# SCH_nfc_card_2024-08-14.net
KiCad netlist of a schematic drawn in EasyEDA
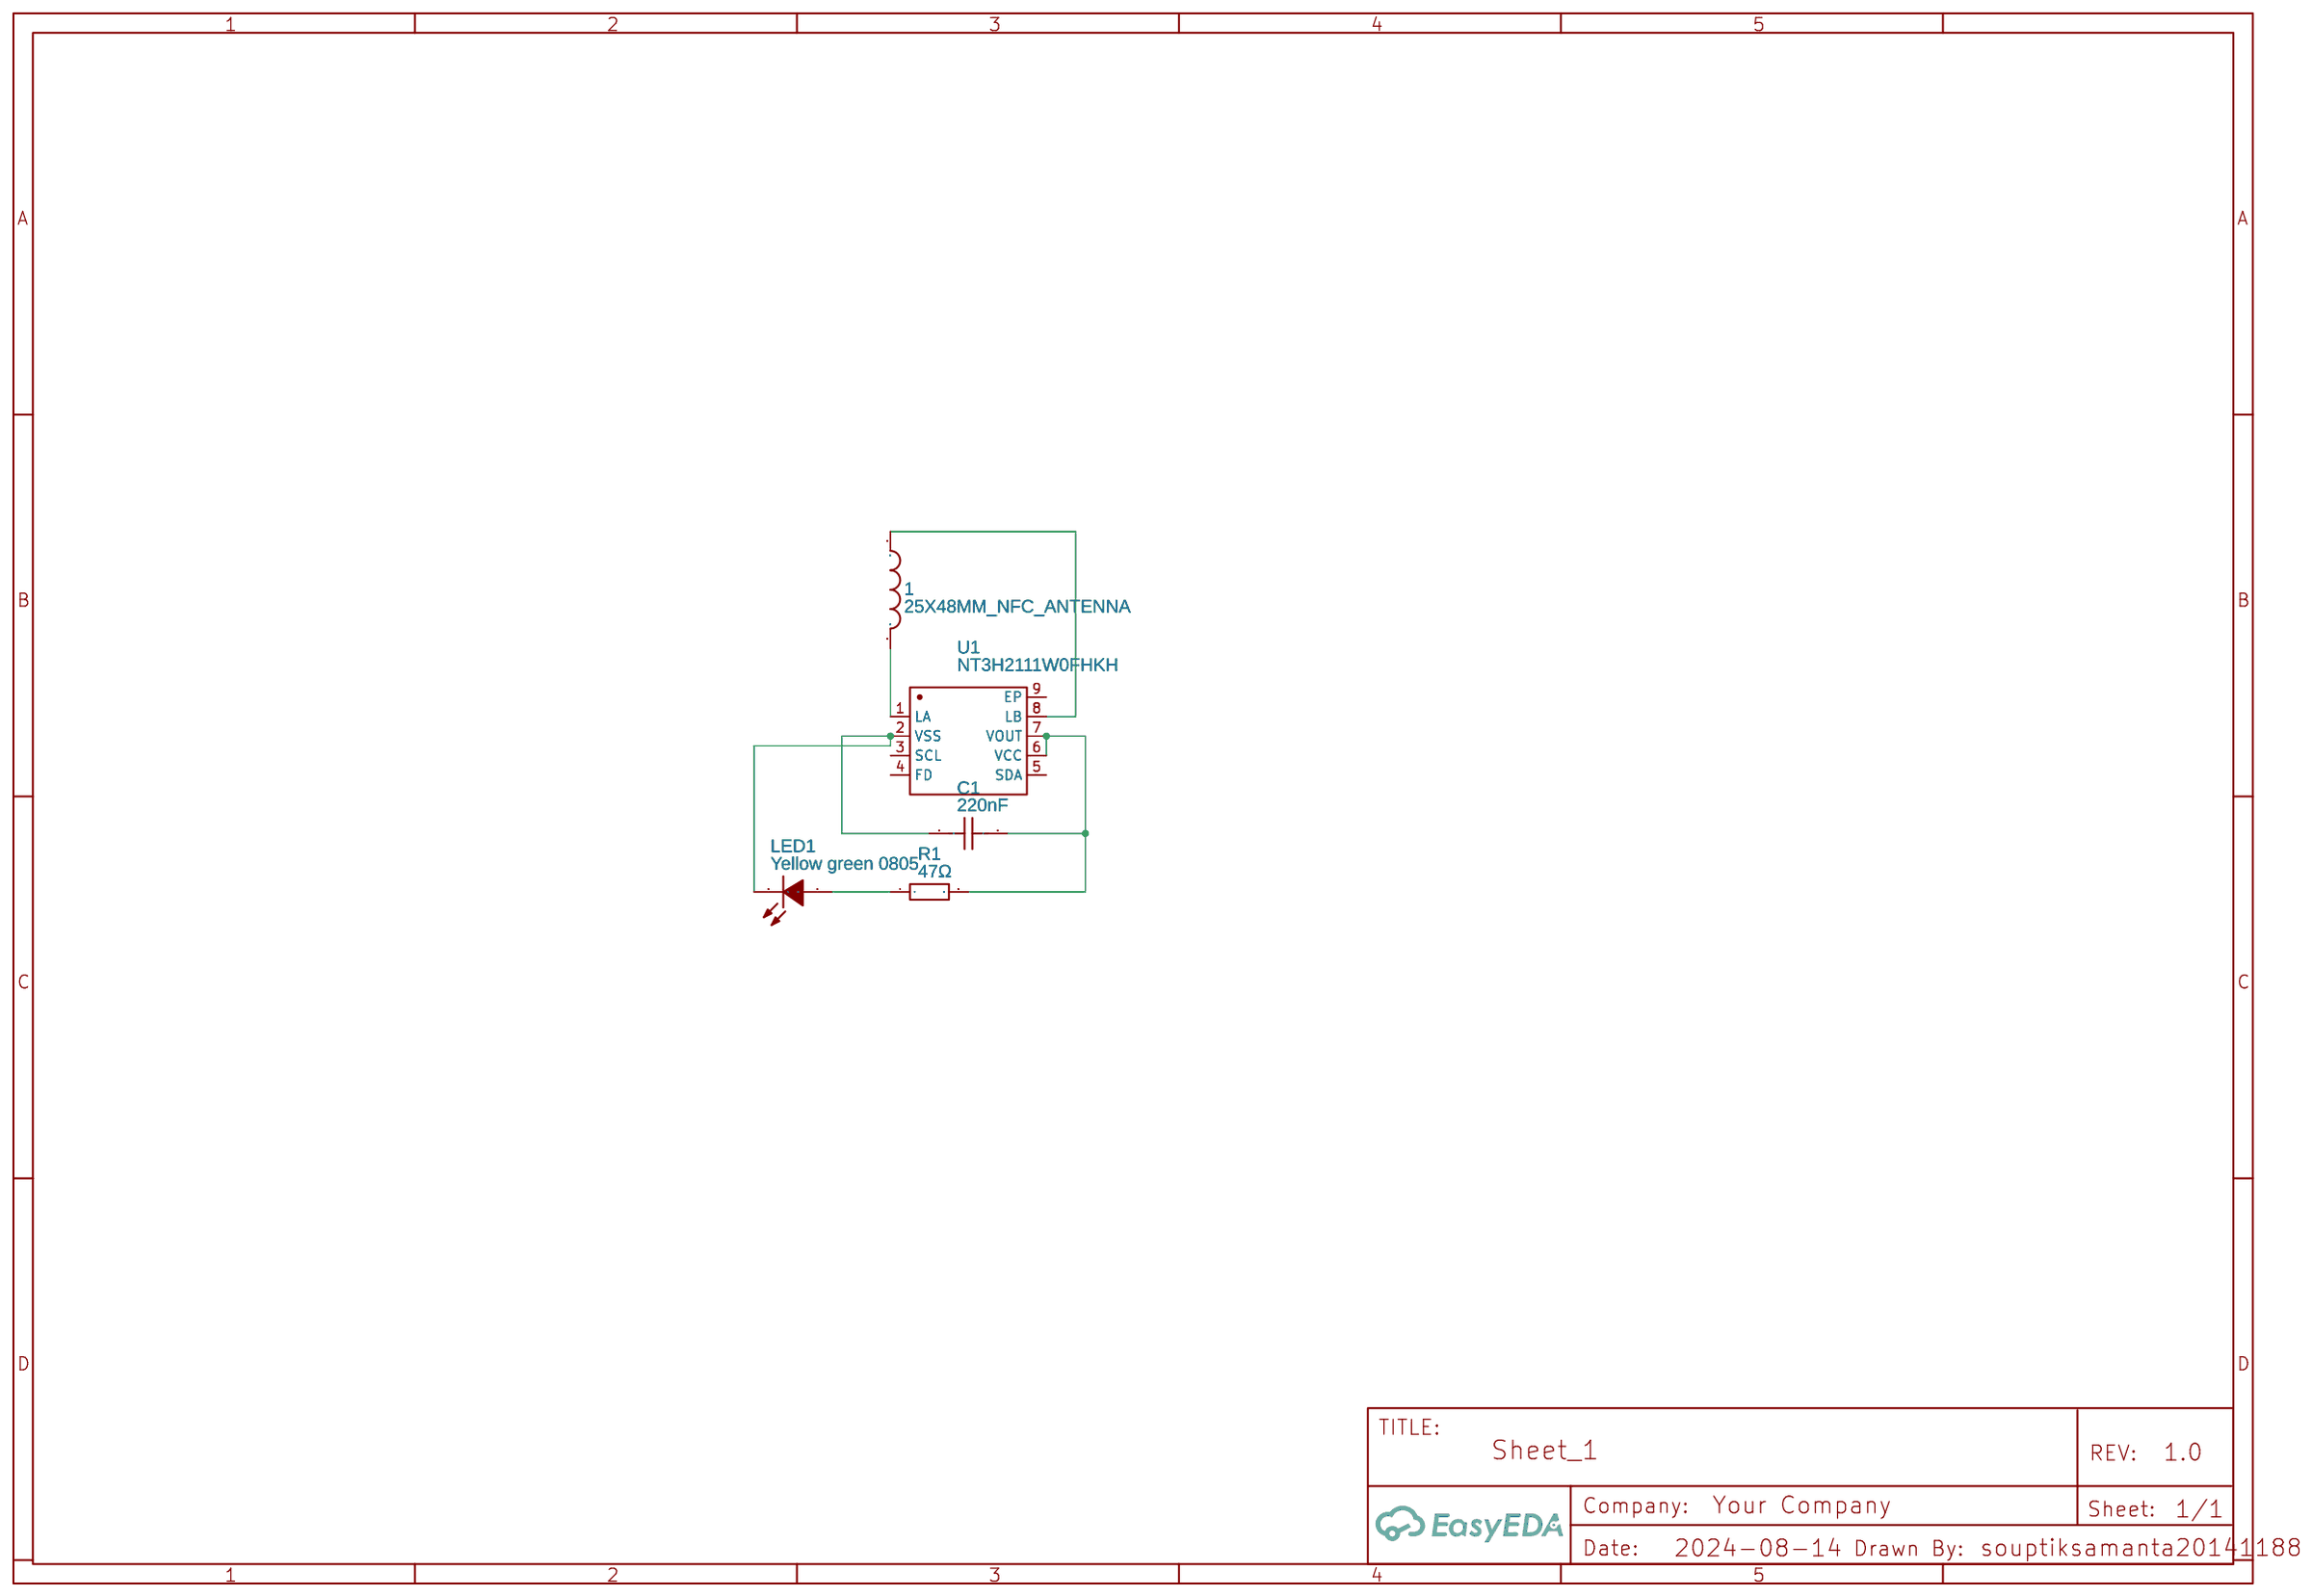
[diagram p0: schematic sheet]

(export (version "E")
  (design (tool "Eeschema 10.0.6"))
  (components
    (comp (ref "1") (value "25X48MM_NFC_ANTENNA") (libsource (lib "") (part "25X48MM_NFC_ANTENNA")))
    (comp (ref "C1")
      (value "220nF")
      (fields (field (name "Manufacturer Part") "0805B224K500NT") (field (name "Manufacturer") "FH(风华)"))
      (libsource (lib "") (part "0805B224K500NT"))
    )
    (comp (ref "LED1")
      (value "Yellow green 0805")
      (fields (field (name "Manufacturer Part") "KT-0805YG") (field (name "Manufacturer") "KENTO"))
      (libsource (lib "") (part "Yellow green 0805"))
    )
    (comp (ref "R1")
      (value "47Ω")
      (fields
        (field (name "Manufacturer Part") "0603WAF470JT5E")
        (field (name "Manufacturer") "UNI-ROYAL(厚声)")
      )
      (libsource (lib "") (part "0603WAF470JT5E"))
    )
    (comp (ref "U1")
      (value "NT3H2111W0FHKH")
      (fields (field (name "Manufacturer") "NXP(恩智浦)"))
      (libsource (lib "") (part "NT3H2111W0FHKH"))
    )
  )
  (nets
    (net (code "1") (name "Net-(LED1-A)") (class "Default")
      (node (ref "LED1") (pin "1") (pinfunction "A_1") (pintype "unspecified"))
      (node (ref "R1") (pin "1") (pinfunction "1_1") (pintype "input"))
    )
    (net (code "2") (name "Net-(LED1-K)") (class "Default")
      (node (ref "C1") (pin "2") (pinfunction "2_2") (pintype "unspecified"))
      (node (ref "LED1") (pin "2") (pinfunction "K_2") (pintype "unspecified"))
      (node (ref "U1") (pin "2") (pinfunction "VSS_2") (pintype "unspecified"))
    )
    (net (code "3") (name "Net-(U1-LA)") (class "Default")
      (node (ref "1") (pin "P$2") (pinfunction "P$2_P$2") (pintype "bidirectional"))
      (node (ref "U1") (pin "1") (pinfunction "LA_1") (pintype "unspecified"))
    )
    (net (code "4") (name "Net-(U1-LB)") (class "Default")
      (node (ref "1") (pin "P$1") (pinfunction "P$1_P$1") (pintype "bidirectional"))
      (node (ref "U1") (pin "8") (pinfunction "LB_8") (pintype "unspecified"))
    )
    (net (code "5") (name "Net-(U1-VCC)") (class "Default")
      (node (ref "C1") (pin "1") (pinfunction "1_1") (pintype "unspecified"))
      (node (ref "R1") (pin "2") (pinfunction "2_2") (pintype "input"))
      (node (ref "U1") (pin "6") (pinfunction "VCC_6") (pintype "unspecified"))
      (node (ref "U1") (pin "7") (pinfunction "VOUT_7") (pintype "unspecified"))
    )
    (net (code "6") (name "unconnected-(U1-EP-Pad9)") (class "Default")
      (node (ref "U1") (pin "9") (pinfunction "EP_9") (pintype "unspecified"))
    )
    (net (code "7") (name "unconnected-(U1-FD-Pad4)") (class "Default")
      (node (ref "U1") (pin "4") (pinfunction "FD_4") (pintype "unspecified"))
    )
    (net (code "8") (name "unconnected-(U1-SCL-Pad3)") (class "Default")
      (node (ref "U1") (pin "3") (pinfunction "SCL_3") (pintype "unspecified"))
    )
    (net (code "9") (name "unconnected-(U1-SDA-Pad5)") (class "Default")
      (node (ref "U1") (pin "5") (pinfunction "SDA_5") (pintype "unspecified"))
    )
  )
)
